# SparkFun_Simultaneous_RFID_Reader_M7E.net
KiCad netlist of a schematic drawn in EAGLE
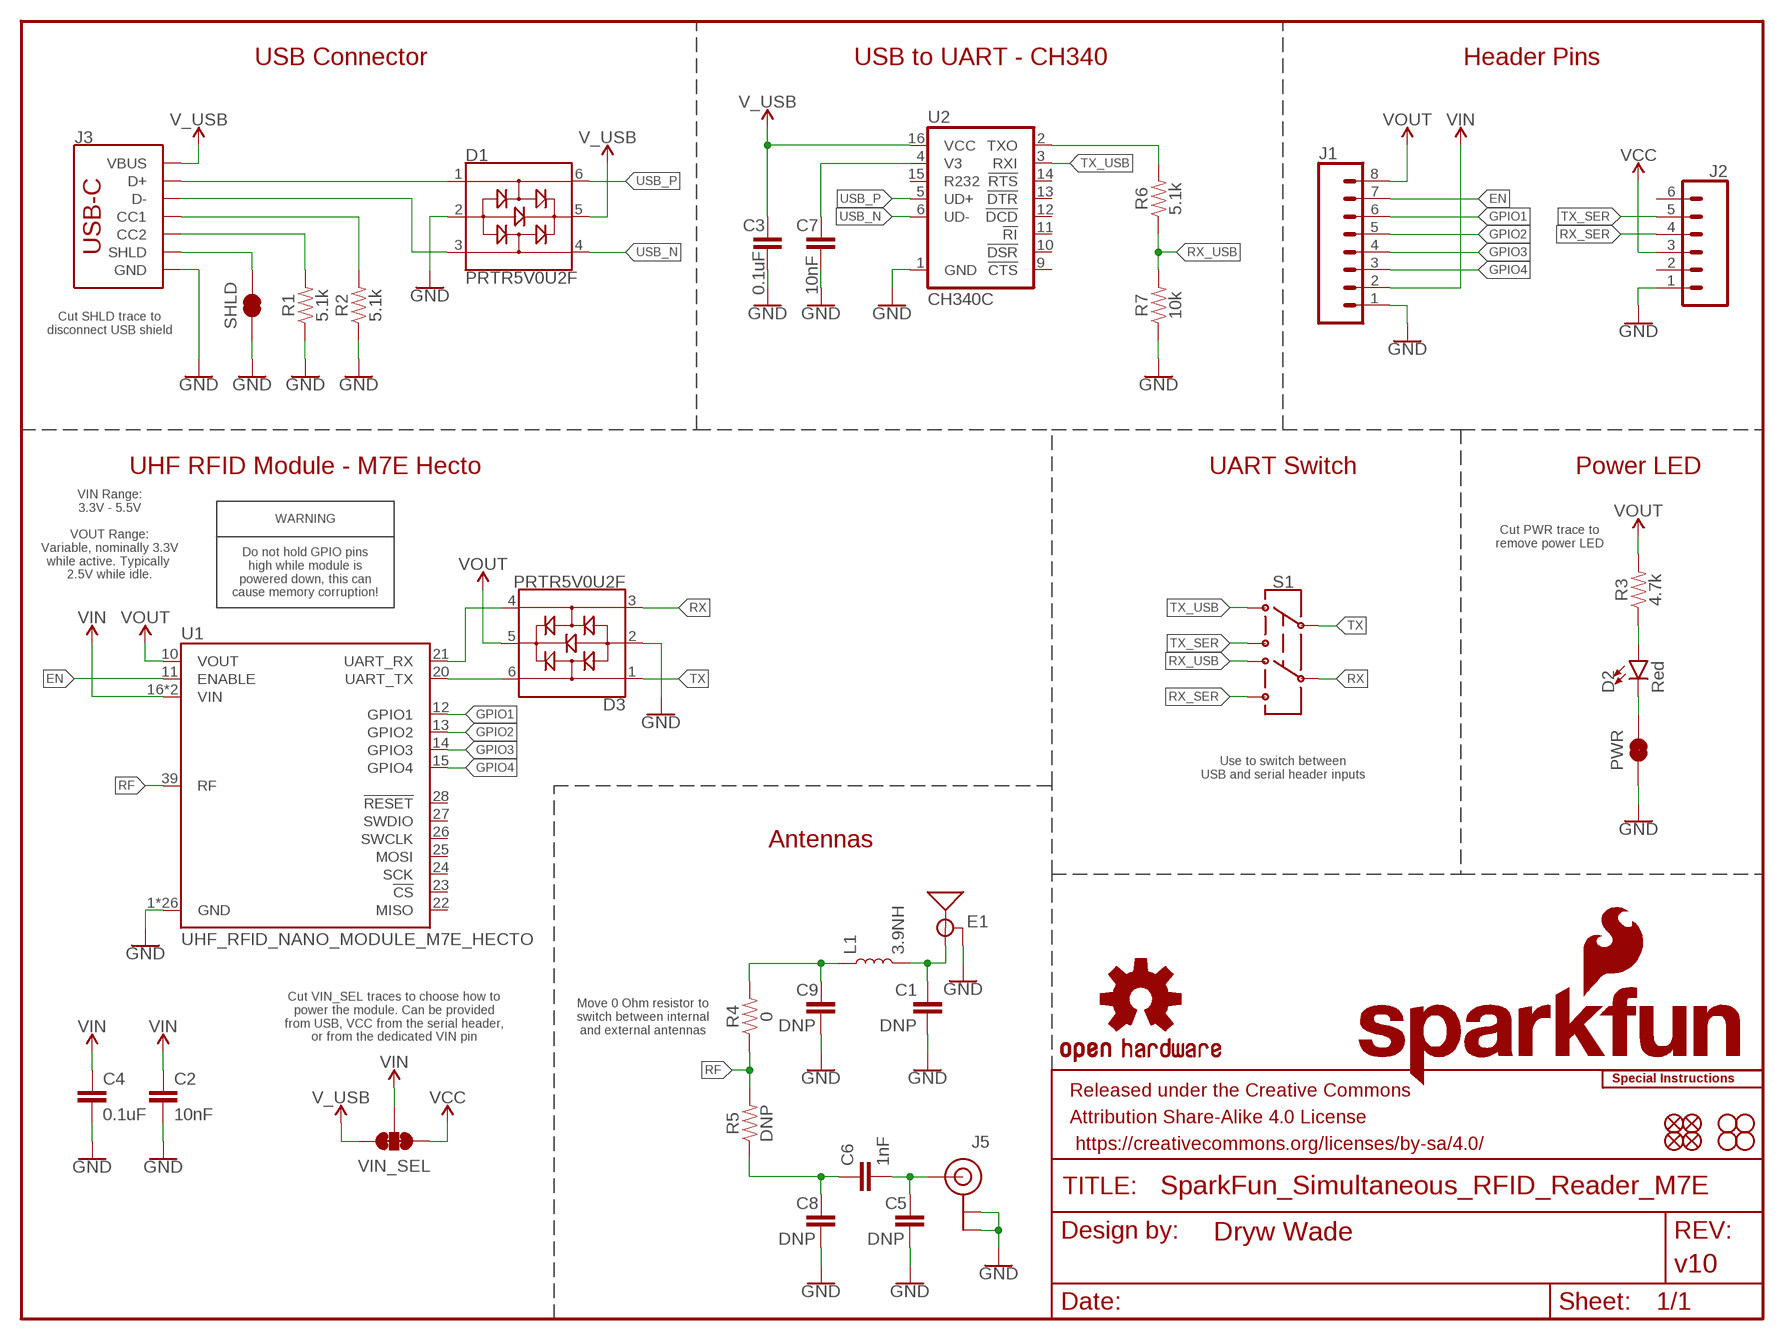
[diagram p0: schematic, sheet 1]

(export (version "E")
  (design (tool "Eeschema 10.0.6"))
  (components
    (comp (ref "C1")
      (value "DNP")
      (footprint "eagle-import:0603")
      (libsource (lib "eagle-import") (part "1.0PF-0603-50V-25%"))
    )
    (comp (ref "C2")
      (value "10nF")
      (footprint "eagle-import:0603")
      (libsource (lib "eagle-import") (part "10NF-0603-50V-10%"))
    )
    (comp (ref "C3")
      (value "0.1uF")
      (footprint "eagle-import:0603")
      (libsource (lib "eagle-import") (part "0.1UF-0603-25V-(+80/-20%)"))
    )
    (comp (ref "C4")
      (value "0.1uF")
      (footprint "eagle-import:0603")
      (libsource (lib "eagle-import") (part "0.1UF-0603-25V-(+80/-20%)"))
    )
    (comp (ref "C5")
      (value "DNP")
      (footprint "eagle-import:0603")
      (libsource (lib "eagle-import") (part "1.0PF-0603-50V-25%"))
    )
    (comp (ref "C6")
      (value "1nF")
      (footprint "eagle-import:0603")
      (libsource (lib "eagle-import") (part "1.0NF/1000PF-0603-50V-10%"))
    )
    (comp (ref "C7")
      (value "10nF")
      (footprint "eagle-import:0603")
      (libsource (lib "eagle-import") (part "10NF-0603-50V-10%"))
    )
    (comp (ref "C8")
      (value "DNP")
      (footprint "eagle-import:0603")
      (libsource (lib "eagle-import") (part "1.0PF-0603-50V-25%"))
    )
    (comp (ref "C9")
      (value "DNP")
      (footprint "eagle-import:0603")
      (libsource (lib "eagle-import") (part "1.0PF-0603-50V-25%"))
    )
    (comp (ref "D1")
      (value "PRTR5V0U2F")
      (footprint "eagle-import:SOT886")
      (libsource (lib "eagle-import") (part "PRTR5V0U2F"))
    )
    (comp (ref "D2")
      (value "Red")
      (footprint "eagle-import:LED-0603")
      (libsource (lib "eagle-import") (part "LED-RED_0603-KB"))
    )
    (comp (ref "D3")
      (value "PRTR5V0U2F")
      (footprint "eagle-import:SOT886")
      (libsource (lib "eagle-import") (part "PRTR5V0U2F"))
    )
    (comp (ref "E1")
      (value "ANTENNA-GROUNDEDTRACE-915MHZ")
      (footprint "eagle-import:TRACE_ANTENNA_915MHZ_THINGMAGIC")
      (libsource (lib "eagle-import") (part "ANTENNA-GROUNDEDTRACE-915MHZ"))
    )
    (comp (ref "FD1")
      (value "FIDUCIAL1X2")
      (footprint "eagle-import:FIDUCIAL-1X2")
      (libsource (lib "eagle-import") (part "FIDUCIAL1X2"))
    )
    (comp (ref "FD2")
      (value "FIDUCIAL1X2")
      (footprint "eagle-import:FIDUCIAL-1X2")
      (libsource (lib "eagle-import") (part "FIDUCIAL1X2"))
    )
    (comp (ref "FD3")
      (value "FIDUCIAL1X2")
      (footprint "eagle-import:FIDUCIAL-1X2")
      (libsource (lib "eagle-import") (part "FIDUCIAL1X2"))
    )
    (comp (ref "FD4")
      (value "FIDUCIAL1X2")
      (footprint "eagle-import:FIDUCIAL-1X2")
      (libsource (lib "eagle-import") (part "FIDUCIAL1X2"))
    )
    (comp (ref "FRAME1")
      (value "FRAME-LETTER")
      (footprint "eagle-import:CREATIVE_COMMONS")
      (fields (field (name "DESIGNER") "Dryw Wade") (field (name "REV") "v10"))
      (libsource (lib "eagle-import") (part "FRAME-LETTER"))
    )
    (comp (ref "H1")
      (value "STAND-OFF")
      (footprint "eagle-import:STAND-OFF")
      (libsource (lib "eagle-import") (part "STAND-OFF"))
    )
    (comp (ref "H2")
      (value "STAND-OFF")
      (footprint "eagle-import:STAND-OFF")
      (libsource (lib "eagle-import") (part "STAND-OFF"))
    )
    (comp (ref "H3")
      (value "STAND-OFF")
      (footprint "eagle-import:STAND-OFF")
      (libsource (lib "eagle-import") (part "STAND-OFF"))
    )
    (comp (ref "H4")
      (value "STAND-OFF")
      (footprint "eagle-import:STAND-OFF")
      (libsource (lib "eagle-import") (part "STAND-OFF"))
    )
    (comp (ref "J1")
      (value "CONN_08NO_SILK_DNP")
      (footprint "eagle-import:1X08_NO_SILK")
      (libsource (lib "eagle-import") (part "CONN_08NO_SILK_DNP"))
    )
    (comp (ref "J2")
      (value "CONN_06NO_SILK_NO_POP")
      (footprint "eagle-import:1X06_NO_SILK")
      (libsource (lib "eagle-import") (part "CONN_06NO_SILK_NO_POP"))
    )
    (comp (ref "J3")
      (value "USB_C_2-LAYER_PADS")
      (footprint "eagle-import:USB-C-16P-2LAYER-PADS")
      (libsource (lib "eagle-import") (part "USB_C_2-LAYER_PADS"))
    )
    (comp (ref "J5")
      (value "U.FL")
      (footprint "eagle-import:U.FL")
      (libsource (lib "eagle-import") (part "U.FL"))
    )
    (comp (ref "L1")
      (value "3.9NH")
      (footprint "eagle-import:0603")
      (libsource (lib "eagle-import") (part "3.9NH"))
    )
    (comp (ref "LOGO1")
      (value "OSHW-LOGOM")
      (footprint "eagle-import:OSHW-LOGO-M")
      (libsource (lib "eagle-import") (part "OSHW-LOGOM"))
    )
    (comp (ref "LOGO2")
      (value "SFE_LOGO_NAME_FLAME.2_INCH")
      (footprint "eagle-import:SFE_LOGO_NAME_FLAME_.2")
      (libsource (lib "eagle-import") (part "SFE_LOGO_NAME_FLAME.2_INCH"))
    )
    (comp (ref "LOGO3")
      (value "SFE_LOGO_NAME_FLAME.2_INCH")
      (footprint "eagle-import:SFE_LOGO_NAME_FLAME_.2")
      (libsource (lib "eagle-import") (part "SFE_LOGO_NAME_FLAME.2_INCH"))
    )
    (comp (ref "LOGO4")
      (value "SPECIAL_INSTRUCTIONS-ORDERING")
      (footprint "eagle-import:ORDERING_INSTRUCTIONS")
      (libsource (lib "eagle-import") (part "SPECIAL_INSTRUCTIONS-ORDERING"))
    )
    (comp (ref "PWR")
      (value "JUMPER-SMT_2_NC_TRACE_SILK")
      (footprint "eagle-import:SMT-JUMPER_2_NC_TRACE_SILK")
      (libsource (lib "eagle-import") (part "JUMPER-SMT_2_NC_TRACE_SILK"))
    )
    (comp (ref "R1")
      (value "5.1k")
      (footprint "eagle-import:0603")
      (libsource (lib "eagle-import") (part "5.1KOHM5.1KOHM-0603-1/10W-1%"))
    )
    (comp (ref "R2")
      (value "5.1k")
      (footprint "eagle-import:0603")
      (libsource (lib "eagle-import") (part "5.1KOHM5.1KOHM-0603-1/10W-1%"))
    )
    (comp (ref "R3")
      (value "4.7k")
      (footprint "eagle-import:0603")
      (libsource (lib "eagle-import") (part "4.7KOHM-0603-1/10W-1%"))
    )
    (comp (ref "R4")
      (value "0")
      (footprint "eagle-import:0603")
      (libsource (lib "eagle-import") (part "0OHM-0603-1/10W"))
    )
    (comp (ref "R5")
      (value "DNP")
      (footprint "eagle-import:0603")
      (libsource (lib "eagle-import") (part "0OHM-0603-1/10W"))
    )
    (comp (ref "R6")
      (value "5.1k")
      (footprint "eagle-import:0603")
      (libsource (lib "eagle-import") (part "5.1KOHM5.1KOHM-0603-1/10W-1%"))
    )
    (comp (ref "R7")
      (value "10k")
      (footprint "eagle-import:0603")
      (libsource (lib "eagle-import") (part "10KOHM-0603-1/10W-1%"))
    )
    (comp (ref "S1")
      (value "SWITCH-DPDT-SMD-AYZ0202")
      (footprint "eagle-import:SWITCH_DPDT_SMD_AYZ0202")
      (libsource (lib "eagle-import") (part "SWITCH-DPDT-SMD-AYZ0202"))
    )
    (comp (ref "SHLD")
      (value "JUMPER-SMT_2_NC_TRACE_SILK")
      (footprint "eagle-import:SMT-JUMPER_2_NC_TRACE_SILK")
      (libsource (lib "eagle-import") (part "JUMPER-SMT_2_NC_TRACE_SILK"))
    )
    (comp (ref "U1")
      (value "UHF_RFID_NANO_MODULE_M7E_HECTO")
      (footprint "eagle-import:M7E_HECTO_MODULE")
      (libsource (lib "eagle-import") (part "UHF_RFID_NANO_MODULE_M7E_HECTO"))
    )
    (comp (ref "U2")
      (value "CH340C")
      (footprint "eagle-import:SO016")
      (libsource (lib "eagle-import") (part "CH340C"))
    )
    (comp (ref "VIN_SEL")
      (value "JUMPER-SMT_3_2-NC_TRACE_SILK")
      (footprint "eagle-import:SMT-JUMPER_3_2-NC_TRACE_SILK")
      (libsource (lib "eagle-import") (part "JUMPER-SMT_3_2-NC_TRACE_SILK"))
    )
  )
  (nets
    (net (code "1") (name "EN") (class "Default")
      (node (ref "J1") (pin "7") (pinfunction "7_7") (pintype "passive"))
      (node (ref "U1") (pin "11") (pinfunction "ENABLE_11") (pintype "bidirectional"))
    )
    (net (code "2") (name "GND") (class "Default")
      (node (ref "C1") (pin "2") (pinfunction "2_2") (pintype "passive"))
      (node (ref "C2") (pin "2") (pinfunction "2_2") (pintype "passive"))
      (node (ref "C3") (pin "2") (pinfunction "2_2") (pintype "passive"))
      (node (ref "C4") (pin "2") (pinfunction "2_2") (pintype "passive"))
      (node (ref "C5") (pin "2") (pinfunction "2_2") (pintype "passive"))
      (node (ref "C7") (pin "2") (pinfunction "2_2") (pintype "passive"))
      (node (ref "C8") (pin "2") (pinfunction "2_2") (pintype "passive"))
      (node (ref "C9") (pin "2") (pinfunction "2_2") (pintype "passive"))
      (node (ref "D1") (pin "2") (pinfunction "2_2") (pintype "power_in"))
      (node (ref "D3") (pin "2") (pinfunction "2_2") (pintype "power_in"))
      (node (ref "E1") (pin "GND@1") (pinfunction "GND_GND@1") (pintype "bidirectional"))
      (node (ref "E1") (pin "GND@2") (pinfunction "GND_GND@2") (pintype "bidirectional"))
      (node (ref "E1") (pin "GND@3") (pinfunction "GND_GND@3") (pintype "bidirectional"))
      (node (ref "J1") (pin "1") (pinfunction "1_1") (pintype "passive"))
      (node (ref "J2") (pin "1") (pinfunction "1_1") (pintype "passive"))
      (node (ref "J3") (pin "GND") (pinfunction "GND_GND") (pintype "bidirectional"))
      (node (ref "J3") (pin "GND2") (pinfunction "GND_GND2") (pintype "bidirectional"))
      (node (ref "J5") (pin "1") (pinfunction "GND_1") (pintype "bidirectional"))
      (node (ref "J5") (pin "2") (pinfunction "GND_2") (pintype "bidirectional"))
      (node (ref "PWR") (pin "1") (pinfunction "1_1") (pintype "passive"))
      (node (ref "R1") (pin "1") (pinfunction "1_1") (pintype "passive"))
      (node (ref "R2") (pin "1") (pinfunction "1_1") (pintype "passive"))
      (node (ref "R7") (pin "1") (pinfunction "1_1") (pintype "passive"))
      (node (ref "SHLD") (pin "1") (pinfunction "1_1") (pintype "passive"))
      (node (ref "U1") (pin "1") (pinfunction "GND_1") (pintype "bidirectional"))
      (node (ref "U1") (pin "18") (pinfunction "GND_18") (pintype "bidirectional"))
      (node (ref "U1") (pin "19") (pinfunction "GND_19") (pintype "bidirectional"))
      (node (ref "U1") (pin "2") (pinfunction "GND_2") (pintype "bidirectional"))
      (node (ref "U1") (pin "29") (pinfunction "GND_29") (pintype "bidirectional"))
      (node (ref "U1") (pin "3") (pinfunction "GND_3") (pintype "bidirectional"))
      (node (ref "U1") (pin "30") (pinfunction "GND_30") (pintype "bidirectional"))
      (node (ref "U1") (pin "31") (pinfunction "GND_31") (pintype "bidirectional"))
      (node (ref "U1") (pin "32") (pinfunction "GND_32") (pintype "bidirectional"))
      (node (ref "U1") (pin "33") (pinfunction "GND_33") (pintype "bidirectional"))
      (node (ref "U1") (pin "34") (pinfunction "GND_34") (pintype "bidirectional"))
      (node (ref "U1") (pin "35") (pinfunction "GND_35") (pintype "bidirectional"))
      (node (ref "U1") (pin "36") (pinfunction "GND_36") (pintype "bidirectional"))
      (node (ref "U1") (pin "37") (pinfunction "GND_37") (pintype "bidirectional"))
      (node (ref "U1") (pin "38") (pinfunction "GND_38") (pintype "bidirectional"))
      (node (ref "U1") (pin "4") (pinfunction "GND_4") (pintype "bidirectional"))
      (node (ref "U1") (pin "40") (pinfunction "GND_40") (pintype "bidirectional"))
      (node (ref "U1") (pin "41") (pinfunction "GND_41") (pintype "bidirectional"))
      (node (ref "U1") (pin "5") (pinfunction "GND_5") (pintype "bidirectional"))
      (node (ref "U1") (pin "6") (pinfunction "GND_6") (pintype "bidirectional"))
      (node (ref "U1") (pin "7") (pinfunction "GND_7") (pintype "bidirectional"))
      (node (ref "U1") (pin "8") (pinfunction "GND_8") (pintype "bidirectional"))
      (node (ref "U1") (pin "9") (pinfunction "GND_9") (pintype "bidirectional"))
      (node (ref "U1") (pin "GND_PAD1") (pinfunction "GND_GND_PAD1") (pintype "bidirectional"))
      (node (ref "U1") (pin "GND_PAD2") (pinfunction "GND_GND_PAD2") (pintype "bidirectional"))
      (node (ref "U1") (pin "GND_PAD3") (pinfunction "GND_GND_PAD3") (pintype "bidirectional"))
      (node (ref "U2") (pin "1") (pinfunction "GND_1") (pintype "bidirectional"))
    )
    (net (code "3") (name "GPIO1") (class "Default")
      (node (ref "J1") (pin "6") (pinfunction "6_6") (pintype "passive"))
      (node (ref "U1") (pin "12") (pinfunction "GPIO1_12") (pintype "bidirectional"))
    )
    (net (code "4") (name "GPIO2") (class "Default")
      (node (ref "J1") (pin "5") (pinfunction "5_5") (pintype "passive"))
      (node (ref "U1") (pin "13") (pinfunction "GPIO2_13") (pintype "bidirectional"))
    )
    (net (code "5") (name "GPIO3") (class "Default")
      (node (ref "J1") (pin "4") (pinfunction "4_4") (pintype "passive"))
      (node (ref "U1") (pin "14") (pinfunction "GPIO3_14") (pintype "bidirectional"))
    )
    (net (code "6") (name "GPIO4") (class "Default")
      (node (ref "J1") (pin "3") (pinfunction "3_3") (pintype "passive"))
      (node (ref "U1") (pin "15") (pinfunction "GPIO4_15") (pintype "bidirectional"))
    )
    (net (code "7") (name "Net-(C6-Pad1)") (class "Default")
      (node (ref "C6") (pin "1") (pinfunction "1_1") (pintype "passive"))
      (node (ref "C8") (pin "1") (pinfunction "1_1") (pintype "passive"))
      (node (ref "R5") (pin "1") (pinfunction "1_1") (pintype "passive"))
    )
    (net (code "8") (name "Net-(C9-Pad1)") (class "Default")
      (node (ref "C9") (pin "1") (pinfunction "1_1") (pintype "passive"))
      (node (ref "L1") (pin "1") (pinfunction "1_1") (pintype "passive"))
      (node (ref "R4") (pin "2") (pinfunction "2_2") (pintype "passive"))
    )
    (net (code "9") (name "Net-(D1-Pad1)") (class "Default")
      (node (ref "D1") (pin "1") (pinfunction "1_1") (pintype "bidirectional"))
      (node (ref "J3") (pin "A6") (pinfunction "D+_A6") (pintype "bidirectional"))
      (node (ref "J3") (pin "B6") (pinfunction "D+_B6") (pintype "bidirectional"))
    )
    (net (code "10") (name "Net-(D1-Pad3)") (class "Default")
      (node (ref "D1") (pin "3") (pinfunction "3_3") (pintype "bidirectional"))
      (node (ref "J3") (pin "A7") (pinfunction "D-_A7") (pintype "bidirectional"))
      (node (ref "J3") (pin "B7") (pinfunction "D-_B7") (pintype "bidirectional"))
    )
    (net (code "11") (name "Net-(D2-PadA)") (class "Default")
      (node (ref "D2") (pin "A") (pinfunction "A_A") (pintype "passive"))
      (node (ref "R3") (pin "1") (pinfunction "1_1") (pintype "passive"))
    )
    (net (code "12") (name "Net-(D2-PadC)") (class "Default")
      (node (ref "D2") (pin "C") (pinfunction "C_C") (pintype "passive"))
      (node (ref "PWR") (pin "2") (pinfunction "2_2") (pintype "passive"))
    )
    (net (code "13") (name "Net-(E1-SIGNAL)") (class "Default")
      (node (ref "C1") (pin "1") (pinfunction "1_1") (pintype "passive"))
      (node (ref "E1") (pin "ANT") (pinfunction "SIGNAL_ANT") (pintype "bidirectional"))
      (node (ref "L1") (pin "2") (pinfunction "2_2") (pintype "passive"))
    )
    (net (code "14") (name "Net-(J3-CC1)") (class "Default")
      (node (ref "J3") (pin "A5") (pinfunction "CC1_A5") (pintype "bidirectional"))
      (node (ref "R2") (pin "2") (pinfunction "2_2") (pintype "passive"))
    )
    (net (code "15") (name "Net-(J3-CC2)") (class "Default")
      (node (ref "J3") (pin "B5") (pinfunction "CC2_B5") (pintype "bidirectional"))
      (node (ref "R1") (pin "2") (pinfunction "2_2") (pintype "passive"))
    )
    (net (code "16") (name "Net-(J3-SHLD-PadSHLD1)") (class "Default")
      (node (ref "J3") (pin "SHLD1") (pinfunction "SHLD_SHLD1") (pintype "bidirectional"))
      (node (ref "J3") (pin "SHLD2") (pinfunction "SHLD_SHLD2") (pintype "bidirectional"))
      (node (ref "J3") (pin "SHLD3") (pinfunction "SHLD_SHLD3") (pintype "bidirectional"))
      (node (ref "J3") (pin "SHLD4") (pinfunction "SHLD_SHLD4") (pintype "bidirectional"))
      (node (ref "SHLD") (pin "2") (pinfunction "2_2") (pintype "passive"))
    )
    (net (code "17") (name "Net-(J5-SIGNAL)") (class "Default")
      (node (ref "C5") (pin "1") (pinfunction "1_1") (pintype "passive"))
      (node (ref "C6") (pin "2") (pinfunction "2_2") (pintype "passive"))
      (node (ref "J5") (pin "FEED") (pinfunction "SIGNAL_FEED") (pintype "bidirectional"))
    )
    (net (code "18") (name "Net-(U1-UART_RX)") (class "Default")
      (node (ref "D3") (pin "4") (pinfunction "4_4") (pintype "bidirectional"))
      (node (ref "U1") (pin "21") (pinfunction "UART_RX_21") (pintype "bidirectional"))
    )
    (net (code "19") (name "Net-(U1-UART_TX)") (class "Default")
      (node (ref "D3") (pin "6") (pinfunction "6_6") (pintype "bidirectional"))
      (node (ref "U1") (pin "20") (pinfunction "UART_TX_20") (pintype "bidirectional"))
    )
    (net (code "20") (name "Net-(U2-TXO)") (class "Default")
      (node (ref "R6") (pin "2") (pinfunction "2_2") (pintype "passive"))
      (node (ref "U2") (pin "2") (pinfunction "TXO_2") (pintype "bidirectional"))
    )
    (net (code "21") (name "Net-(U2-V3)") (class "Default")
      (node (ref "C7") (pin "1") (pinfunction "1_1") (pintype "passive"))
      (node (ref "U2") (pin "4") (pinfunction "V3_4") (pintype "bidirectional"))
    )
    (net (code "22") (name "RF") (class "Default")
      (node (ref "R4") (pin "1") (pinfunction "1_1") (pintype "passive"))
      (node (ref "R5") (pin "2") (pinfunction "2_2") (pintype "passive"))
      (node (ref "U1") (pin "39") (pinfunction "RF_39") (pintype "bidirectional"))
    )
    (net (code "23") (name "RX") (class "Default")
      (node (ref "D3") (pin "3") (pinfunction "3_3") (pintype "bidirectional"))
      (node (ref "S1") (pin "5") (pinfunction "5_5") (pintype "bidirectional"))
    )
    (net (code "24") (name "RX_SER") (class "Default")
      (node (ref "J2") (pin "4") (pinfunction "4_4") (pintype "passive"))
      (node (ref "S1") (pin "4") (pinfunction "4_4") (pintype "bidirectional"))
    )
    (net (code "25") (name "RX_USB") (class "Default")
      (node (ref "R6") (pin "1") (pinfunction "1_1") (pintype "passive"))
      (node (ref "R7") (pin "2") (pinfunction "2_2") (pintype "passive"))
      (node (ref "S1") (pin "6") (pinfunction "6_6") (pintype "bidirectional"))
    )
    (net (code "26") (name "TX") (class "Default")
      (node (ref "D3") (pin "1") (pinfunction "1_1") (pintype "bidirectional"))
      (node (ref "S1") (pin "2") (pinfunction "2_2") (pintype "bidirectional"))
    )
    (net (code "27") (name "TX_SER") (class "Default")
      (node (ref "J2") (pin "5") (pinfunction "5_5") (pintype "passive"))
      (node (ref "S1") (pin "1") (pinfunction "1_1") (pintype "bidirectional"))
    )
    (net (code "28") (name "TX_USB") (class "Default")
      (node (ref "S1") (pin "3") (pinfunction "3_3") (pintype "bidirectional"))
      (node (ref "U2") (pin "3") (pinfunction "RXI_3") (pintype "bidirectional"))
    )
    (net (code "29") (name "USB_N") (class "Default")
      (node (ref "D1") (pin "4") (pinfunction "4_4") (pintype "bidirectional"))
      (node (ref "U2") (pin "6") (pinfunction "UD-_6") (pintype "bidirectional"))
    )
    (net (code "30") (name "USB_P") (class "Default")
      (node (ref "D1") (pin "6") (pinfunction "6_6") (pintype "bidirectional"))
      (node (ref "U2") (pin "5") (pinfunction "UD+_5") (pintype "bidirectional"))
    )
    (net (code "31") (name "VCC") (class "Default")
      (node (ref "J2") (pin "3") (pinfunction "3_3") (pintype "passive"))
      (node (ref "VIN_SEL") (pin "1") (pinfunction "1_1") (pintype "passive"))
    )
    (net (code "32") (name "VIN") (class "Default")
      (node (ref "C2") (pin "1") (pinfunction "1_1") (pintype "passive"))
      (node (ref "C4") (pin "1") (pinfunction "1_1") (pintype "passive"))
      (node (ref "J1") (pin "2") (pinfunction "2_2") (pintype "passive"))
      (node (ref "U1") (pin "16") (pinfunction "VIN_16") (pintype "bidirectional"))
      (node (ref "U1") (pin "17") (pinfunction "VIN_17") (pintype "bidirectional"))
      (node (ref "VIN_SEL") (pin "2") (pinfunction "2_2") (pintype "passive"))
    )
    (net (code "33") (name "VOUT") (class "Default")
      (node (ref "D3") (pin "5") (pinfunction "5_5") (pintype "power_in"))
      (node (ref "J1") (pin "8") (pinfunction "8_8") (pintype "passive"))
      (node (ref "R3") (pin "2") (pinfunction "2_2") (pintype "passive"))
      (node (ref "U1") (pin "10") (pinfunction "VOUT_10") (pintype "bidirectional"))
    )
    (net (code "34") (name "V_USB") (class "Default")
      (node (ref "C3") (pin "1") (pinfunction "1_1") (pintype "passive"))
      (node (ref "D1") (pin "5") (pinfunction "5_5") (pintype "power_in"))
      (node (ref "J3") (pin "VBUS1") (pinfunction "VBUS_VBUS1") (pintype "bidirectional"))
      (node (ref "J3") (pin "VBUS2") (pinfunction "VBUS_VBUS2") (pintype "bidirectional"))
      (node (ref "U2") (pin "16") (pinfunction "VCC_16") (pintype "bidirectional"))
      (node (ref "VIN_SEL") (pin "3") (pinfunction "3_3") (pintype "passive"))
    )
    (net (code "35") (name "unconnected-(J2-Pad2)") (class "Default")
      (node (ref "J2") (pin "2") (pinfunction "2_2") (pintype "passive"))
    )
    (net (code "36") (name "unconnected-(J2-Pad6)") (class "Default")
      (node (ref "J2") (pin "6") (pinfunction "6_6") (pintype "passive"))
    )
    (net (code "37") (name "unconnected-(U1-MISO-Pad22)") (class "Default")
      (node (ref "U1") (pin "22") (pinfunction "MISO_22") (pintype "bidirectional"))
    )
    (net (code "38") (name "unconnected-(U1-MOSI-Pad25)") (class "Default")
      (node (ref "U1") (pin "25") (pinfunction "MOSI_25") (pintype "bidirectional"))
    )
    (net (code "39") (name "unconnected-(U1-SCK-Pad24)") (class "Default")
      (node (ref "U1") (pin "24") (pinfunction "SCK_24") (pintype "bidirectional"))
    )
    (net (code "40") (name "unconnected-(U1-SWCLK-Pad26)") (class "Default")
      (node (ref "U1") (pin "26") (pinfunction "SWCLK_26") (pintype "bidirectional"))
    )
    (net (code "41") (name "unconnected-(U1-SWDIO-Pad27)") (class "Default")
      (node (ref "U1") (pin "27") (pinfunction "SWDIO_27") (pintype "bidirectional"))
    )
    (net (code "42") (name "unconnected-(U1-~{CS}-Pad23)") (class "Default")
      (node (ref "U1") (pin "23") (pinfunction "~{CS}_23") (pintype "bidirectional"))
    )
    (net (code "43") (name "unconnected-(U1-~{RESET}-Pad28)") (class "Default")
      (node (ref "U1") (pin "28") (pinfunction "~{RESET}_28") (pintype "bidirectional"))
    )
    (net (code "44") (name "unconnected-(U2-R232-Pad15)") (class "Default")
      (node (ref "U2") (pin "15") (pinfunction "R232_15") (pintype "bidirectional"))
    )
    (net (code "45") (name "unconnected-(U2-~{CTS}-Pad9)") (class "Default")
      (node (ref "U2") (pin "9") (pinfunction "~{CTS}_9") (pintype "bidirectional"))
    )
    (net (code "46") (name "unconnected-(U2-~{DCD}-Pad12)") (class "Default")
      (node (ref "U2") (pin "12") (pinfunction "~{DCD}_12") (pintype "bidirectional"))
    )
    (net (code "47") (name "unconnected-(U2-~{DSR}-Pad10)") (class "Default")
      (node (ref "U2") (pin "10") (pinfunction "~{DSR}_10") (pintype "bidirectional"))
    )
    (net (code "48") (name "unconnected-(U2-~{DTR}-Pad13)") (class "Default")
      (node (ref "U2") (pin "13") (pinfunction "~{DTR}_13") (pintype "bidirectional"))
    )
    (net (code "49") (name "unconnected-(U2-~{RI}-Pad11)") (class "Default")
      (node (ref "U2") (pin "11") (pinfunction "~{RI}_11") (pintype "bidirectional"))
    )
    (net (code "50") (name "unconnected-(U2-~{RTS}-Pad14)") (class "Default")
      (node (ref "U2") (pin "14") (pinfunction "~{RTS}_14") (pintype "bidirectional"))
    )
  )
)
